# Offboard_Outputs.net
KiCad netlist of a schematic drawn in Altium Designer
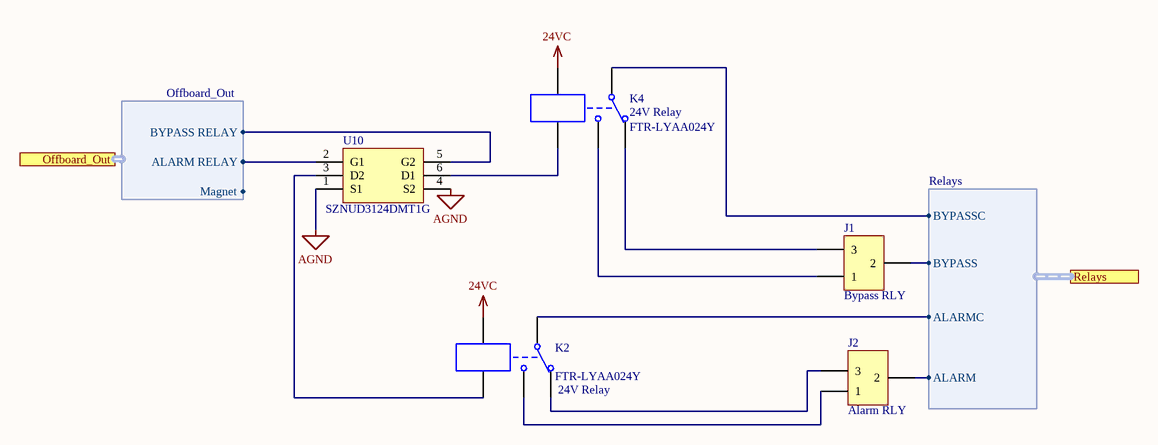
[diagram p0: Offboard_Outputs.SchDoc]

(export (version "E")
  (design (tool "Eeschema 10.0.6"))
  (components
    (comp (ref "J1")
      (value "Bypass RLY")
      (footprint "3 Pin Header for Relay")
      (description "Header, 3-Pin")
      (libsource (lib "Custom Components") (part "Header 3"))
    )
    (comp (ref "J2")
      (value "Alarm RLY")
      (footprint "3 Pin Header for Relay")
      (description "Header, 3-Pin")
      (libsource (lib "") (part "Header 3_1"))
    )
    (comp (ref "K2")
      (value "24V Relay")
      (footprint "FTR-LY")
      (description "SPST (1 Form A)")
      (fields (field (name "MFR") "Fujitsu") (field (name "MFR P/N") "FTR-LYAA024Y"))
      (libsource (lib "Miscellaneous Devices") (part "Relay-SPDT"))
    )
    (comp (ref "K4")
      (value "24V Relay")
      (footprint "FTR-LY")
      (description "SPST (1 Form A)")
      (fields (field (name "MFR") "Fujitsu") (field (name "MFR P/N") "FTR-LYAA024Y"))
      (libsource (lib "Miscellaneous Devices") (part "Relay-SPDT"))
    )
    (comp (ref "U10")
      (value "SZNUD3124DMT1G")
      (footprint "TI SOT-23-6 DDC")
      (description "Gate Drivers 24 V DUAL INDUCTIVE LOAD")
      (fields (field (name "MFR") "ON Semiconductor") (field (name "MFR P/N") "SZNUD3124DMT1G"))
      (libsource (lib "Custom Components") (part "SZNUD3124DMT1G"))
    )
  )
  (nets
    (net (code "3") (name "/ALARM") (class "Default")
      (node (ref "J2") (pin "2") (pinfunction "2_2") (pintype "passive"))
    )
    (net (code "4") (name "/ALARM RELAY") (class "Default")
      (node (ref "U10") (pin "2") (pinfunction "G1_2") (pintype "open_emitter"))
    )
    (net (code "5") (name "/ALARMC") (class "Default")
      (node (ref "K2") (pin "1") (pinfunction "COM_1") (pintype "passive"))
    )
    (net (code "6") (name "/BYPASS") (class "Default")
      (node (ref "J1") (pin "2") (pinfunction "2_2") (pintype "passive"))
    )
    (net (code "7") (name "/BYPASS RELAY") (class "Default")
      (node (ref "U10") (pin "5") (pinfunction "G2_5") (pintype "tri_state"))
    )
    (net (code "8") (name "/BYPASSC") (class "Default")
      (node (ref "K4") (pin "1") (pinfunction "COM_1") (pintype "passive"))
    )
    (net (code "11") (name "24VC") (class "Default")
      (node (ref "K2") (pin "4") (pinfunction "4_4") (pintype "passive"))
      (node (ref "K4") (pin "4") (pinfunction "4_4") (pintype "passive"))
    )
    (net (code "12") (name "AGND") (class "Default")
      (node (ref "U10") (pin "1") (pinfunction "S1_1") (pintype "passive"))
      (node (ref "U10") (pin "4") (pinfunction "S2_4") (pintype "passive"))
    )
    (net (code "13") (name "Net-(K2-N{slash}C)") (class "Default")
      (node (ref "J2") (pin "3") (pinfunction "3_3") (pintype "passive"))
      (node (ref "K2") (pin "2") (pinfunction "N/C_2") (pintype "passive"))
    )
    (net (code "14") (name "Net-(K2-N{slash}O)") (class "Default")
      (node (ref "J2") (pin "1") (pinfunction "1_1") (pintype "passive"))
      (node (ref "K2") (pin "3") (pinfunction "N/O_3") (pintype "passive"))
    )
    (net (code "15") (name "Net-(K4-N{slash}C)") (class "Default")
      (node (ref "J1") (pin "3") (pinfunction "3_3") (pintype "passive"))
      (node (ref "K4") (pin "2") (pinfunction "N/C_2") (pintype "passive"))
    )
    (net (code "16") (name "Net-(K4-N{slash}O)") (class "Default")
      (node (ref "J1") (pin "1") (pinfunction "1_1") (pintype "passive"))
      (node (ref "K4") (pin "3") (pinfunction "N/O_3") (pintype "passive"))
    )
    (net (code "17") (name "Net-(U10-D1)") (class "Default")
      (node (ref "K4") (pin "5") (pinfunction "5_5") (pintype "passive"))
      (node (ref "U10") (pin "6") (pinfunction "D1_6") (pintype "passive"))
    )
    (net (code "18") (name "Net-(U10-D2)") (class "Default")
      (node (ref "K2") (pin "5") (pinfunction "5_5") (pintype "passive"))
      (node (ref "U10") (pin "3") (pinfunction "D2_3") (pintype "passive"))
    )
  )
)
